# MainBoardNew.net
KiCad netlist of a schematic drawn in Altium Designer
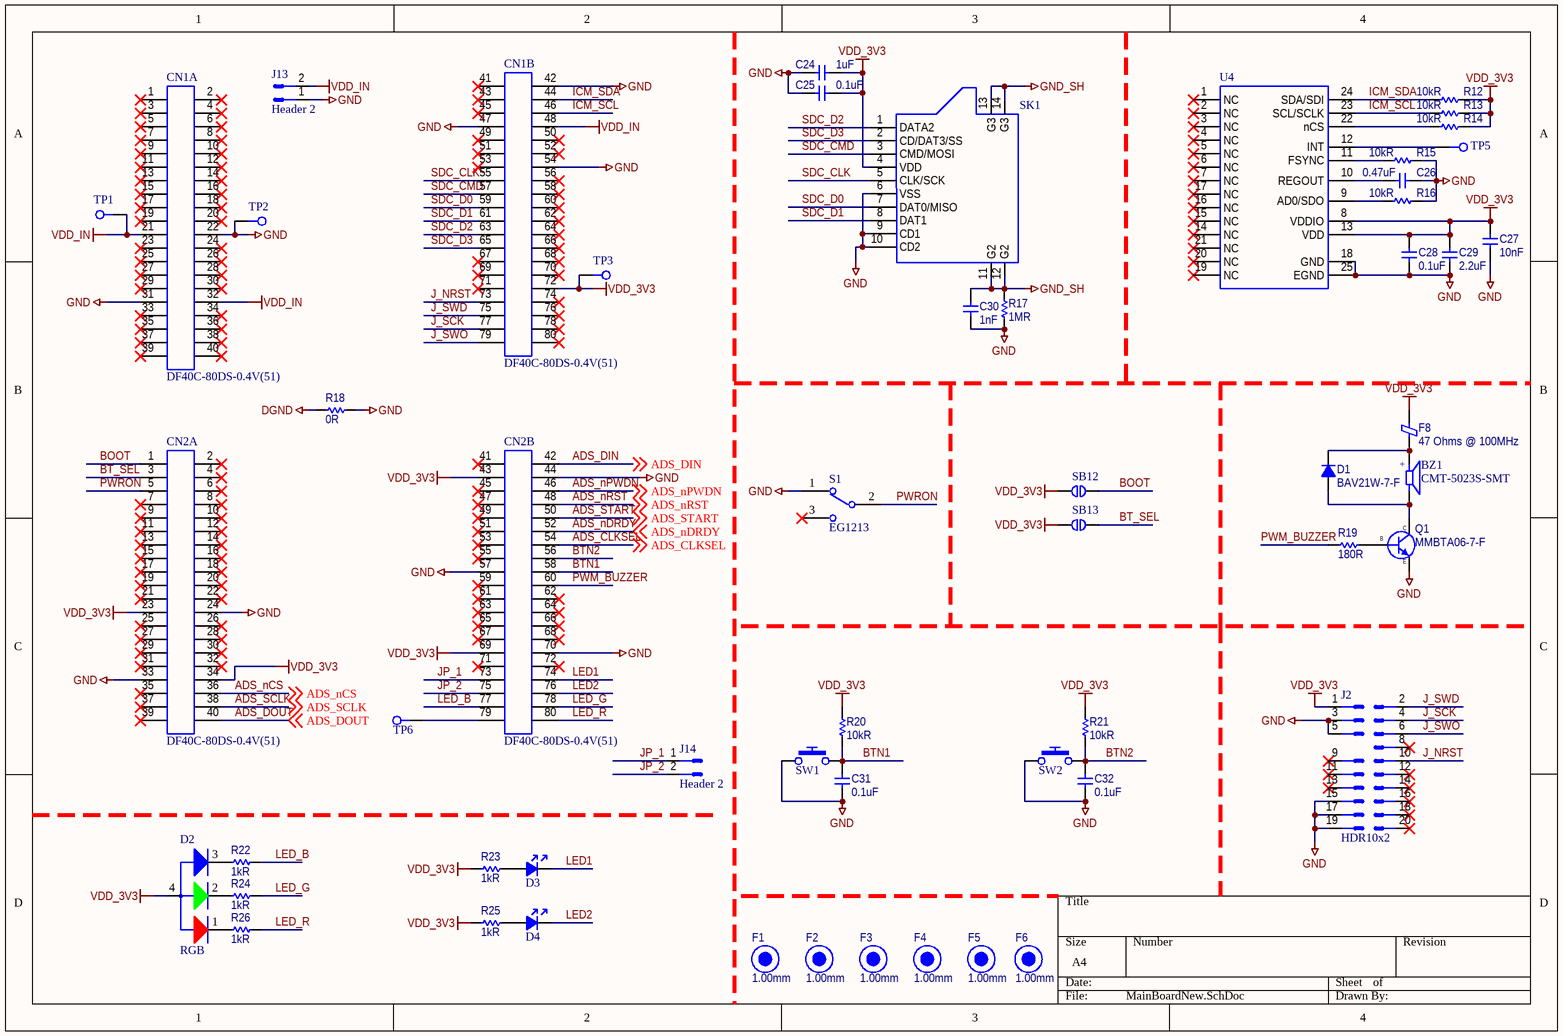
[diagram p0: MainBoardNew.SchDoc]

(export (version "E")
  (design (tool "Eeschema 10.0.6"))
  (components
    (comp (ref "BZ1")
      (value "CMT-5023S-SMT")
      (footprint "CUI_CMT-5023S-SMT")
      (description "AUDIO MAGNETIC XDCR 2-4V SMD")
      (fields
        (field (name "MANUFACTURER") "CUI Devices")
        (field (name "MANUFACTURER PART NUMBER") "CMT-5023S-SMT-TR")
      )
      (libsource (lib "DungMV") (part "CMT-5023S-SMT"))
    )
    (comp (ref "C24")
      (value "1uF")
      (footprint "C1005X04N")
      (description "CAP CER,1UF,10%,16V,X5R,0402,SMD")
      (fields
        (field (name "MANUFACTURER PART NUMBER") "EMK105BJ105KV-F")
        (field (name "MANUFACTURER") "Taiyo Yuden")
      )
      (libsource (lib "Database Library") (part "C_CAPN"))
    )
    (comp (ref "C25")
      (value "0.1uF")
      (footprint "C1005X04N")
      (description "CAP CER,0.1UF,20%,25V,X5R,0402,SMD")
      (fields
        (field (name "MANUFACTURER PART NUMBER") "TMK105BJ104MV-F")
        (field (name "MANUFACTURER") "Taiyo Yuden")
      )
      (libsource (lib "Database Library") (part "C_CAPN"))
    )
    (comp (ref "C26")
      (value "0.47uF")
      (footprint "C1005X04N")
      (description "CAP CER,0.47UF,10%,25V,X5R,0402,SMD")
      (fields
        (field (name "MANUFACTURER PART NUMBER") "TMK105ABJ474KVHF")
        (field (name "MANUFACTURER") "Taiyo Yuden")
      )
      (libsource (lib "Database Library") (part "C_CAPN"))
    )
    (comp (ref "C27")
      (value "10nF")
      (footprint "C1005X04N")
      (description "CAP CER,10NF,10%,50V,X7R,0402,SMD")
      (fields
        (field (name "MANUFACTURER PART NUMBER") "UMK105B7103KV-F")
        (field (name "MANUFACTURER") "Taiyo Yuden")
      )
      (libsource (lib "Database Library") (part "C_CAPN"))
    )
    (comp (ref "C28")
      (value "0.1uF")
      (footprint "C1005X04N")
      (description "CAP CER,0.1UF,20%,25V,X5R,0402,SMD")
      (fields
        (field (name "MANUFACTURER PART NUMBER") "TMK105BJ104MV-F")
        (field (name "MANUFACTURER") "Taiyo Yuden")
      )
      (libsource (lib "Database Library") (part "C_CAPN"))
    )
    (comp (ref "C29")
      (value "2.2uF")
      (footprint "C1005X04N")
      (description "CAP CER,2.2UF,20%,25V,X5R,0402,SMD")
      (fields
        (field (name "MANUFACTURER PART NUMBER") "TMK105CBJ225MV-F")
        (field (name "MANUFACTURER") "Taiyo Yuden")
      )
      (libsource (lib "Database Library") (part "C_CAPN"))
    )
    (comp (ref "C30")
      (value "1nF")
      (footprint "C1005X04N")
      (description "CAP CER,1NF,10%,50V,X7R,0402,SMD")
      (fields
        (field (name "MANUFACTURER PART NUMBER") "UMK105B7102KV-F")
        (field (name "MANUFACTURER") "Taiyo Yuden")
      )
      (libsource (lib "Database Library") (part "C_CAPN"))
    )
    (comp (ref "C31")
      (value "0.1uF")
      (footprint "C1005X04N")
      (description "CAP CER,0.1UF,20%,25V,X5R,0402,SMD")
      (fields
        (field (name "MANUFACTURER PART NUMBER") "TMK105BJ104MV-F")
        (field (name "MANUFACTURER") "Taiyo Yuden")
      )
      (libsource (lib "Database Library") (part "C_CAPN"))
    )
    (comp (ref "C32")
      (value "0.1uF")
      (footprint "C1005X04N")
      (description "CAP CER,0.1UF,20%,25V,X5R,0402,SMD")
      (fields
        (field (name "MANUFACTURER PART NUMBER") "TMK105BJ104MV-F")
        (field (name "MANUFACTURER") "Taiyo Yuden")
      )
      (libsource (lib "Database Library") (part "C_CAPN"))
    )
    (comp (ref "CN1")
      (value "DF40C-80DS-0.4V(51)")
      (footprint "DF40C-80DS-0.4V(51)")
      (description "CONN RCPT 80POS SMD GOLD")
      (fields (field (name "MANUFACTURER") "Hirose Electric Co Ltd"))
      (libsource (lib "DungMV") (part "DF40C-80DS-0.4V(51)"))
    )
    (comp (ref "CN2")
      (value "DF40C-80DS-0.4V(51)")
      (footprint "DF40C-80DS-0.4V(51)")
      (description "CONN RCPT 80POS SMD GOLD")
      (fields (field (name "MANUFACTURER") "Hirose Electric Co Ltd"))
      (libsource (lib "DungMV") (part "DF40C-80DS-0.4V(51)"))
    )
    (comp (ref "D1")
      (value "BAV21W-7-F")
      (footprint "SOD123")
      (description "DIODE,200V,200MA,1-CH,ID,SOD-123,SMD")
      (fields (field (name "MANUFACTURER") "Diodes Incorporated"))
      (libsource (lib "Database Library") (part "D_STD"))
    )
    (comp (ref "D2")
      (value "RGB")
      (footprint "LED 3528 PLCC4 RGB")
      (description "3528 PLCC4 RGB")
      (fields
        (field (name "MANUFACTURER") "American Bright Optoelectronics Corporation")
        (field (name "MANUFACTURER PART NUMBER") "BL-HJXGXBX32M-A")
      )
      (libsource (lib "DungMV") (part "BL-HJXGXBX32M-A"))
    )
    (comp (ref "D3")
      (value "LED BLUE")
      (footprint "LED0603")
      (description "LED BLUE CLEAR CHIP SMD")
      (libsource (lib "DungMV") (part "LTST-C191TBKT"))
    )
    (comp (ref "D4")
      (value "LED BLUE")
      (footprint "LED0603")
      (description "LED BLUE CLEAR CHIP SMD")
      (libsource (lib "DungMV") (part "LTST-C191TBKT"))
    )
    (comp (ref "F1")
      (value "1.00mm")
      (footprint "FIDUCIAL10-30")
      (description "FIDUCIAL,1.00mm,3.00mm")
      (fields
        (field (name "MANUFACTURER PART NUMBER") "FIDUCIAL10-30")
        (field (name "MANUFACTURER") "VNPT-Technology")
      )
      (libsource (lib "Database Library") (part "F_FIDUCIAL"))
    )
    (comp (ref "F2")
      (value "1.00mm")
      (footprint "FIDUCIAL10-30")
      (description "FIDUCIAL,1.00mm,3.00mm")
      (fields
        (field (name "MANUFACTURER PART NUMBER") "FIDUCIAL10-30")
        (field (name "MANUFACTURER") "VNPT-Technology")
      )
      (libsource (lib "Database Library") (part "F_FIDUCIAL"))
    )
    (comp (ref "F3")
      (value "1.00mm")
      (footprint "FIDUCIAL10-30")
      (description "FIDUCIAL,1.00mm,3.00mm")
      (fields
        (field (name "MANUFACTURER PART NUMBER") "FIDUCIAL10-30")
        (field (name "MANUFACTURER") "VNPT-Technology")
      )
      (libsource (lib "Database Library") (part "F_FIDUCIAL"))
    )
    (comp (ref "F4")
      (value "1.00mm")
      (footprint "FIDUCIAL10-30")
      (description "FIDUCIAL,1.00mm,3.00mm")
      (fields
        (field (name "MANUFACTURER PART NUMBER") "FIDUCIAL10-30")
        (field (name "MANUFACTURER") "VNPT-Technology")
      )
      (libsource (lib "Database Library") (part "F_FIDUCIAL"))
    )
    (comp (ref "F5")
      (value "1.00mm")
      (footprint "FIDUCIAL10-30")
      (description "FIDUCIAL,1.00mm,3.00mm")
      (fields
        (field (name "MANUFACTURER PART NUMBER") "FIDUCIAL10-30")
        (field (name "MANUFACTURER") "VNPT-Technology")
      )
      (libsource (lib "Database Library") (part "F_FIDUCIAL"))
    )
    (comp (ref "F6")
      (value "1.00mm")
      (footprint "FIDUCIAL10-30")
      (description "FIDUCIAL,1.00mm,3.00mm")
      (fields
        (field (name "MANUFACTURER PART NUMBER") "FIDUCIAL10-30")
        (field (name "MANUFACTURER") "VNPT-Technology")
      )
      (libsource (lib "Database Library") (part "F_FIDUCIAL"))
    )
    (comp (ref "F8")
      (value "47 Ohms @ 100MHz")
      (footprint "F2012X06N")
      (description "FERRITE BEAD,47 OHMS @ 100MHZ,0.05R,1A,0805,SMD")
      (fields
        (field (name "MANUFACTURER PART NUMBER") "BK2125HS470-T")
        (field (name "MANUFACTURER") "Taiyo Yuden")
      )
      (libsource (lib "Database Library") (part "F_FERRITE_BEAD"))
    )
    (comp (ref "J2")
      (value "HDR10x2")
      (footprint "FTSH-110-01-L-DV-007-P-TR")
      (description "CONN HEADER SMD 20POS 1.27MM")
      (libsource (lib "DungMV") (part "FTSH-110-01-L-DV-007-P-TR"))
    )
    (comp (ref "J13") (value "Header 2") (footprint "HDR1x2") (libsource (lib "DungMV") (part "Header 2")))
    (comp (ref "J14") (value "Header 2") (footprint "HDR1x2") (libsource (lib "DungMV") (part "Header 2")))
    (comp (ref "Q1")
      (value "MMBTA06-7-F")
      (footprint "SOT95P245X110-3N")
      (description "BJT NPN,80V,500MA,SOT23-3,SMD")
      (fields (field (name "MANUFACTURER") "Diodes Incorporated"))
      (libsource (lib "Database Library") (part "Q_NPN"))
    )
    (comp (ref "R12")
      (value "10kR")
      (footprint "R1005X04N")
      (description "RES,10KR,1%,62.5MW,0402,SMD")
      (fields
        (field (name "MANUFACTURER PART NUMBER") "RC0402FR-0710KL")
        (field (name "MANUFACTURER") "Yageo")
      )
      (libsource (lib "Database Library") (part "R_RES"))
    )
    (comp (ref "R13")
      (value "10kR")
      (footprint "R1005X04N")
      (description "RES,10KR,1%,62.5MW,0402,SMD")
      (fields
        (field (name "MANUFACTURER PART NUMBER") "RC0402FR-0710KL")
        (field (name "MANUFACTURER") "Yageo")
      )
      (libsource (lib "Database Library") (part "R_RES"))
    )
    (comp (ref "R14")
      (value "10kR")
      (footprint "R1005X04N")
      (description "RES,10KR,1%,62.5MW,0402,SMD")
      (fields
        (field (name "MANUFACTURER PART NUMBER") "RC0402FR-0710KL")
        (field (name "MANUFACTURER") "Yageo")
      )
      (libsource (lib "Database Library") (part "R_RES"))
    )
    (comp (ref "R15")
      (value "10kR")
      (footprint "R1005X04N")
      (description "RES,10KR,1%,62.5MW,0402,SMD")
      (fields
        (field (name "MANUFACTURER PART NUMBER") "RC0402FR-0710KL")
        (field (name "MANUFACTURER") "Yageo")
      )
      (libsource (lib "Database Library") (part "R_RES"))
    )
    (comp (ref "R16")
      (value "10kR")
      (footprint "R1005X04N")
      (description "RES,10KR,1%,62.5MW,0402,SMD")
      (fields
        (field (name "MANUFACTURER PART NUMBER") "RC0402FR-0710KL")
        (field (name "MANUFACTURER") "Yageo")
      )
      (libsource (lib "Database Library") (part "R_RES"))
    )
    (comp (ref "R17")
      (value "1MR")
      (footprint "R1005X04N")
      (description "RES,1MR,1%,62.5MW,0402,SMD")
      (fields
        (field (name "MANUFACTURER PART NUMBER") "RC0402FR-071ML")
        (field (name "MANUFACTURER") "Yageo")
      )
      (libsource (lib "Database Library") (part "R_RES"))
    )
    (comp (ref "R18")
      (value "0R")
      (footprint "R1005X04N")
      (description "RES,0R,JUMPER,62.5MW,0402,SMD")
      (fields
        (field (name "MANUFACTURER PART NUMBER") "RC0402FR-070RL")
        (field (name "MANUFACTURER") "Yageo")
      )
      (libsource (lib "Database Library") (part "R_RES"))
    )
    (comp (ref "R19")
      (value "180R")
      (footprint "R1005X04N")
      (description "RES,180R,1%,200MW,0402,SMD")
      (fields
        (field (name "MANUFACTURER PART NUMBER") "CRCW0402180RFKEDHP")
        (field (name "MANUFACTURER") "Vishay / Dale")
      )
      (libsource (lib "Database Library") (part "R_RES"))
    )
    (comp (ref "R20")
      (value "10kR")
      (footprint "R1005X04N")
      (description "RES,10KR,1%,62.5MW,0402,SMD")
      (fields
        (field (name "MANUFACTURER PART NUMBER") "RC0402FR-0710KL")
        (field (name "MANUFACTURER") "Yageo")
      )
      (libsource (lib "Database Library") (part "R_RES"))
    )
    (comp (ref "R21")
      (value "10kR")
      (footprint "R1005X04N")
      (description "RES,10KR,1%,62.5MW,0402,SMD")
      (fields
        (field (name "MANUFACTURER PART NUMBER") "RC0402FR-0710KL")
        (field (name "MANUFACTURER") "Yageo")
      )
      (libsource (lib "Database Library") (part "R_RES"))
    )
    (comp (ref "R22")
      (value "1kR")
      (footprint "R1005X04N")
      (description "RES,1KR,5%,62.5MW,0402,SMD")
      (fields
        (field (name "MANUFACTURER PART NUMBER") "RC0402JR-071KL")
        (field (name "MANUFACTURER") "Yageo")
      )
      (libsource (lib "Database Library") (part "R_RES"))
    )
    (comp (ref "R23")
      (value "1kR")
      (footprint "R1005X04N")
      (description "RES,1KR,5%,62.5MW,0402,SMD")
      (fields
        (field (name "MANUFACTURER PART NUMBER") "RC0402JR-071KL")
        (field (name "MANUFACTURER") "Yageo")
      )
      (libsource (lib "Database Library") (part "R_RES"))
    )
    (comp (ref "R24")
      (value "1kR")
      (footprint "R1005X04N")
      (description "RES,1KR,5%,62.5MW,0402,SMD")
      (fields
        (field (name "MANUFACTURER PART NUMBER") "RC0402JR-071KL")
        (field (name "MANUFACTURER") "Yageo")
      )
      (libsource (lib "Database Library") (part "R_RES"))
    )
    (comp (ref "R25")
      (value "1kR")
      (footprint "R1005X04N")
      (description "RES,1KR,5%,62.5MW,0402,SMD")
      (fields
        (field (name "MANUFACTURER PART NUMBER") "RC0402JR-071KL")
        (field (name "MANUFACTURER") "Yageo")
      )
      (libsource (lib "Database Library") (part "R_RES"))
    )
    (comp (ref "R26")
      (value "1kR")
      (footprint "R1005X04N")
      (description "RES,1KR,5%,62.5MW,0402,SMD")
      (fields
        (field (name "MANUFACTURER PART NUMBER") "RC0402JR-071KL")
        (field (name "MANUFACTURER") "Yageo")
      )
      (libsource (lib "Database Library") (part "R_RES"))
    )
    (comp (ref "S1")
      (value "EG1213")
      (footprint "SW_EG1213")
      (description "SWITCH SLIDE SPDT 200MA 30V")
      (fields (field (name "MANUFACTURER") "E-Switch"))
      (libsource (lib "DungMV") (part "EG1213"))
    )
    (comp (ref "SB12")
      (value "Solder Jump")
      (footprint "SJB_0603")
      (description "Solder Bridge Jumper 0603")
      (libsource (lib "DungMV") (part "Solder Jump"))
    )
    (comp (ref "SB13")
      (value "Solder Jump")
      (footprint "SJB_0603")
      (description "Solder Bridge Jumper 0603")
      (libsource (lib "DungMV") (part "Solder Jump"))
    )
    (comp (ref "SK1")
      (value "MICRO SD CARD")
      (footprint "114-00841-68")
      (description "CONN MICRO SD CARD PUSH-PULL R/A")
      (fields
        (field (name "MANUFACTURER") "Amphenol ICC (Commercial Products)")
        (field (name "MANUFACTURER PART NUMBER") "114-00841-68")
      )
      (libsource (lib "DungMV") (part "114-00841-68"))
    )
    (comp (ref "SW1")
      (value "FSMRA4JH04")
      (footprint "1-1825027-1")
      (description "SWITCH TACTILE SPST-NO 0.05A 24V")
      (fields (field (name "MANUFACTURER") "TE Connectivity"))
      (libsource (lib "DungMV") (part "FSMRA4JH04"))
    )
    (comp (ref "SW2")
      (value "FSMRA4JH04")
      (footprint "1-1825027-1")
      (description "SWITCH TACTILE SPST-NO 0.05A 24V")
      (fields (field (name "MANUFACTURER") "TE Connectivity"))
      (libsource (lib "DungMV") (part "FSMRA4JH04"))
    )
    (comp (ref "TP1")
      (value "TP_25MILC")
      (footprint "TESTPOINT_1MM")
      (description "Test Point 25mil")
      (libsource (lib "DungMV") (part "TP_25MILC"))
    )
    (comp (ref "TP2")
      (value "TP_25MILC")
      (footprint "TESTPOINT_1MM")
      (description "Test Point 25mil")
      (libsource (lib "DungMV") (part "TP_25MILC"))
    )
    (comp (ref "TP3")
      (value "TP_25MILC")
      (footprint "TESTPOINT_1MM")
      (description "Test Point 25mil")
      (libsource (lib "DungMV") (part "TP_25MILC"))
    )
    (comp (ref "TP5")
      (value "TP_25MILC")
      (footprint "TESTPOINT_1MM")
      (description "Test Point 25mil")
      (libsource (lib "DungMV") (part "TP_25MILC"))
    )
    (comp (ref "TP6")
      (value "TP_25MILC")
      (footprint "TESTPOINT_1MM")
      (description "Test Point 25mil")
      (libsource (lib "DungMV") (part "TP_25MILC"))
    )
    (comp (ref "U4")
      (value "ICM-20689")
      (footprint "QFN50P400X400X100_HS-25N-NP")
      (description "IMU ACCEL/GYRO/MAG I2C/SPI 24QFN")
      (fields (field (name "MANUFACTURER") "TDK InvenSense"))
      (libsource (lib "DungMV") (part "ICM-20689"))
    )
  )
  (nets
    (net (code "1") (name "/BOOT") (class "Default")
      (node (ref "CN2") (pin "1") (pinfunction "1_1") (pintype "passive"))
      (node (ref "SB12") (pin "1") (pinfunction "1_1") (pintype "passive"))
    )
    (net (code "2") (name "/BTN1") (class "Default")
      (node (ref "C31") (pin "2") (pinfunction "2_2") (pintype "passive"))
      (node (ref "CN2") (pin "58") (pinfunction "58_58") (pintype "passive"))
      (node (ref "R20") (pin "1") (pinfunction "1_1") (pintype "passive"))
      (node (ref "SW1") (pin "2") (pinfunction "2_2") (pintype "passive"))
    )
    (net (code "3") (name "/BTN2") (class "Default")
      (node (ref "C32") (pin "2") (pinfunction "2_2") (pintype "passive"))
      (node (ref "CN2") (pin "56") (pinfunction "56_56") (pintype "passive"))
      (node (ref "R21") (pin "1") (pinfunction "1_1") (pintype "passive"))
      (node (ref "SW2") (pin "2") (pinfunction "2_2") (pintype "passive"))
    )
    (net (code "4") (name "/BT_SEL") (class "Default")
      (node (ref "CN2") (pin "3") (pinfunction "3_3") (pintype "passive"))
      (node (ref "SB13") (pin "1") (pinfunction "1_1") (pintype "passive"))
    )
    (net (code "5") (name "/ICM_SCL") (class "Default")
      (node (ref "CN1") (pin "46") (pinfunction "46_46") (pintype "passive"))
      (node (ref "R13") (pin "2") (pinfunction "2_2") (pintype "passive"))
      (node (ref "U4") (pin "23") (pinfunction "SCL/SCLK_23") (pintype "passive"))
    )
    (net (code "6") (name "/ICM_SDA") (class "Default")
      (node (ref "CN1") (pin "44") (pinfunction "44_44") (pintype "passive"))
      (node (ref "R12") (pin "2") (pinfunction "2_2") (pintype "passive"))
      (node (ref "U4") (pin "24") (pinfunction "SDA/SDI_24") (pintype "passive"))
    )
    (net (code "7") (name "/JP_1") (class "Default")
      (node (ref "CN2") (pin "73") (pinfunction "73_73") (pintype "passive"))
      (node (ref "J14") (pin "1") (pinfunction "1_1") (pintype "passive"))
    )
    (net (code "8") (name "/JP_2") (class "Default")
      (node (ref "CN2") (pin "75") (pinfunction "75_75") (pintype "passive"))
      (node (ref "J14") (pin "2") (pinfunction "2_2") (pintype "passive"))
    )
    (net (code "9") (name "/J_NRST") (class "Default")
      (node (ref "CN1") (pin "73") (pinfunction "73_73") (pintype "passive"))
      (node (ref "J2") (pin "10") (pinfunction "10_10") (pintype "passive"))
    )
    (net (code "10") (name "/J_SCK") (class "Default")
      (node (ref "CN1") (pin "77") (pinfunction "77_77") (pintype "passive"))
      (node (ref "J2") (pin "4") (pinfunction "4_4") (pintype "passive"))
    )
    (net (code "11") (name "/J_SWD") (class "Default")
      (node (ref "CN1") (pin "75") (pinfunction "75_75") (pintype "passive"))
      (node (ref "J2") (pin "2") (pinfunction "2_2") (pintype "passive"))
    )
    (net (code "12") (name "/J_SWO") (class "Default")
      (node (ref "CN1") (pin "79") (pinfunction "79_79") (pintype "passive"))
      (node (ref "J2") (pin "6") (pinfunction "6_6") (pintype "passive"))
    )
    (net (code "13") (name "/LED1") (class "Default")
      (node (ref "CN2") (pin "74") (pinfunction "74_74") (pintype "passive"))
      (node (ref "D3") (pin "2") (pinfunction "K_2") (pintype "passive"))
    )
    (net (code "14") (name "/LED2") (class "Default")
      (node (ref "CN2") (pin "76") (pinfunction "76_76") (pintype "passive"))
      (node (ref "D4") (pin "2") (pinfunction "K_2") (pintype "passive"))
    )
    (net (code "15") (name "/LED_B") (class "Default")
      (node (ref "CN2") (pin "77") (pinfunction "77_77") (pintype "passive"))
      (node (ref "R22") (pin "2") (pinfunction "2_2") (pintype "passive"))
    )
    (net (code "16") (name "/LED_G") (class "Default")
      (node (ref "CN2") (pin "78") (pinfunction "78_78") (pintype "passive"))
      (node (ref "R24") (pin "2") (pinfunction "2_2") (pintype "passive"))
    )
    (net (code "17") (name "/LED_R") (class "Default")
      (node (ref "CN2") (pin "80") (pinfunction "80_80") (pintype "passive"))
      (node (ref "R26") (pin "2") (pinfunction "2_2") (pintype "passive"))
    )
    (net (code "18") (name "/PWM_BUZZER") (class "Default")
      (node (ref "CN2") (pin "60") (pinfunction "60_60") (pintype "passive"))
      (node (ref "R19") (pin "1") (pinfunction "1_1") (pintype "passive"))
    )
    (net (code "19") (name "/PWRON") (class "Default")
      (node (ref "CN2") (pin "5") (pinfunction "5_5") (pintype "passive"))
      (node (ref "S1") (pin "2") (pinfunction "2_2") (pintype "passive"))
    )
    (net (code "20") (name "/SDC_CLK") (class "Default")
      (node (ref "CN1") (pin "55") (pinfunction "55_55") (pintype "passive"))
      (node (ref "SK1") (pin "5") (pinfunction "CLK/SCK_5") (pintype "passive"))
    )
    (net (code "21") (name "/SDC_CMD") (class "Default")
      (node (ref "CN1") (pin "57") (pinfunction "57_57") (pintype "passive"))
      (node (ref "SK1") (pin "3") (pinfunction "CMD/MOSI_3") (pintype "passive"))
    )
    (net (code "22") (name "/SDC_D0") (class "Default")
      (node (ref "CN1") (pin "59") (pinfunction "59_59") (pintype "passive"))
      (node (ref "SK1") (pin "7") (pinfunction "DAT0/MISO_7") (pintype "passive"))
    )
    (net (code "23") (name "/SDC_D1") (class "Default")
      (node (ref "CN1") (pin "61") (pinfunction "61_61") (pintype "passive"))
      (node (ref "SK1") (pin "8") (pinfunction "DAT1_8") (pintype "passive"))
    )
    (net (code "24") (name "/SDC_D2") (class "Default")
      (node (ref "CN1") (pin "63") (pinfunction "63_63") (pintype "passive"))
      (node (ref "SK1") (pin "1") (pinfunction "DATA2_1") (pintype "passive"))
    )
    (net (code "25") (name "/SDC_D3") (class "Default")
      (node (ref "CN1") (pin "65") (pinfunction "65_65") (pintype "passive"))
      (node (ref "SK1") (pin "2") (pinfunction "CD/DAT3/SS_2") (pintype "passive"))
    )
    (net (code "26") (name "ADS_CLKSEL") (class "Default")
      (node (ref "CN2") (pin "54") (pinfunction "54_54") (pintype "passive"))
    )
    (net (code "27") (name "ADS_DIN") (class "Default")
      (node (ref "CN2") (pin "42") (pinfunction "42_42") (pintype "passive"))
    )
    (net (code "28") (name "ADS_DOUT") (class "Default")
      (node (ref "CN2") (pin "40") (pinfunction "40_40") (pintype "passive"))
    )
    (net (code "29") (name "ADS_SCLK") (class "Default")
      (node (ref "CN2") (pin "38") (pinfunction "38_38") (pintype "passive"))
    )
    (net (code "30") (name "ADS_START") (class "Default")
      (node (ref "CN2") (pin "50") (pinfunction "50_50") (pintype "passive"))
    )
    (net (code "31") (name "ADS_nCS") (class "Default")
      (node (ref "CN2") (pin "36") (pinfunction "36_36") (pintype "passive"))
    )
    (net (code "32") (name "ADS_nDRDY") (class "Default")
      (node (ref "CN2") (pin "52") (pinfunction "52_52") (pintype "passive"))
    )
    (net (code "33") (name "ADS_nPWDN") (class "Default")
      (node (ref "CN2") (pin "46") (pinfunction "46_46") (pintype "passive"))
    )
    (net (code "34") (name "ADS_nRST") (class "Default")
      (node (ref "CN2") (pin "48") (pinfunction "48_48") (pintype "passive"))
    )
    (net (code "35") (name "DGND") (class "Default")
      (node (ref "R18") (pin "1") (pinfunction "1_1") (pintype "passive"))
    )
    (net (code "36") (name "GND") (class "Default")
      (node (ref "C24") (pin "1") (pinfunction "1_1") (pintype "passive"))
      (node (ref "C25") (pin "2") (pinfunction "2_2") (pintype "passive"))
      (node (ref "C26") (pin "2") (pinfunction "2_2") (pintype "passive"))
      (node (ref "C27") (pin "1") (pinfunction "1_1") (pintype "passive"))
      (node (ref "C28") (pin "2") (pinfunction "2_2") (pintype "passive"))
      (node (ref "C29") (pin "1") (pinfunction "1_1") (pintype "passive"))
      (node (ref "C30") (pin "1") (pinfunction "1_1") (pintype "passive"))
      (node (ref "C31") (pin "1") (pinfunction "1_1") (pintype "passive"))
      (node (ref "C32") (pin "1") (pinfunction "1_1") (pintype "passive"))
      (node (ref "CN1") (pin "22") (pinfunction "22_22") (pintype "passive"))
      (node (ref "CN1") (pin "31") (pinfunction "31_31") (pintype "passive"))
      (node (ref "CN1") (pin "42") (pinfunction "42_42") (pintype "passive"))
      (node (ref "CN1") (pin "47") (pinfunction "47_47") (pintype "passive"))
      (node (ref "CN1") (pin "54") (pinfunction "54_54") (pintype "passive"))
      (node (ref "CN2") (pin "24") (pinfunction "24_24") (pintype "passive"))
      (node (ref "CN2") (pin "33") (pinfunction "33_33") (pintype "passive"))
      (node (ref "CN2") (pin "44") (pinfunction "44_44") (pintype "passive"))
      (node (ref "CN2") (pin "57") (pinfunction "57_57") (pintype "passive"))
      (node (ref "CN2") (pin "70") (pinfunction "70_70") (pintype "passive"))
      (node (ref "J13") (pin "1") (pinfunction "1_1") (pintype "passive"))
      (node (ref "J2") (pin "15") (pinfunction "15_15") (pintype "passive"))
      (node (ref "J2") (pin "17") (pinfunction "17_17") (pintype "passive"))
      (node (ref "J2") (pin "19") (pinfunction "19_19") (pintype "passive"))
      (node (ref "J2") (pin "3") (pinfunction "3_3") (pintype "passive"))
      (node (ref "J2") (pin "5") (pinfunction "5_5") (pintype "passive"))
      (node (ref "Q1") (pin "2") (pinfunction "E_2") (pintype "passive"))
      (node (ref "R15") (pin "1") (pinfunction "1_1") (pintype "passive"))
      (node (ref "R16") (pin "1") (pinfunction "1_1") (pintype "passive"))
      (node (ref "R17") (pin "1") (pinfunction "1_1") (pintype "passive"))
      (node (ref "R18") (pin "2") (pinfunction "2_2") (pintype "passive"))
      (node (ref "S1") (pin "1") (pinfunction "1_1") (pintype "passive"))
      (node (ref "SK1") (pin "10") (pinfunction "CD2_10") (pintype "passive"))
      (node (ref "SK1") (pin "6") (pinfunction "VSS_6") (pintype "power_in"))
      (node (ref "SK1") (pin "9") (pinfunction "CD1_9") (pintype "passive"))
      (node (ref "SW1") (pin "1") (pinfunction "1_1") (pintype "passive"))
      (node (ref "SW2") (pin "1") (pinfunction "1_1") (pintype "passive"))
      (node (ref "TP2") (pin "1") (pinfunction "1_1") (pintype "passive"))
      (node (ref "U4") (pin "18") (pinfunction "GND_18") (pintype "passive"))
      (node (ref "U4") (pin "25") (pinfunction "EGND_25") (pintype "passive"))
    )
    (net (code "37") (name "GND_SH") (class "Default")
      (node (ref "C30") (pin "2") (pinfunction "2_2") (pintype "passive"))
      (node (ref "R17") (pin "2") (pinfunction "2_2") (pintype "passive"))
      (node (ref "SK1") (pin "11") (pinfunction "G2_11") (pintype "power_in"))
      (node (ref "SK1") (pin "12") (pinfunction "G2_12") (pintype "power_in"))
      (node (ref "SK1") (pin "13") (pinfunction "G3_13") (pintype "power_in"))
      (node (ref "SK1") (pin "14") (pinfunction "G3_14") (pintype "power_in"))
    )
    (net (code "38") (name "Net-(CN2-Pad79)") (class "Default")
      (node (ref "CN2") (pin "79") (pinfunction "79_79") (pintype "passive"))
      (node (ref "TP6") (pin "1") (pinfunction "1_1") (pintype "passive"))
    )
    (net (code "39") (name "Net-(D1-A)") (class "Default")
      (node (ref "BZ1") (pin "N") (pinfunction "N_N") (pintype "passive"))
      (node (ref "D1") (pin "2") (pinfunction "A_2") (pintype "passive"))
      (node (ref "Q1") (pin "3") (pinfunction "C_3") (pintype "passive"))
    )
    (net (code "40") (name "Net-(D1-C)") (class "Default")
      (node (ref "BZ1") (pin "P") (pinfunction "P_P") (pintype "passive"))
      (node (ref "D1") (pin "1") (pinfunction "C_1") (pintype "passive"))
      (node (ref "F8") (pin "1") (pinfunction "1_1") (pintype "passive"))
    )
    (net (code "41") (name "Net-(D2-CATHODE_BLUE)") (class "Default")
      (node (ref "D2") (pin "3") (pinfunction "CATHODE_BLUE_3") (pintype "passive"))
      (node (ref "R22") (pin "1") (pinfunction "1_1") (pintype "passive"))
    )
    (net (code "42") (name "Net-(D2-CATHODE_GREEN)") (class "Default")
      (node (ref "D2") (pin "2") (pinfunction "CATHODE_GREEN_2") (pintype "passive"))
      (node (ref "R24") (pin "1") (pinfunction "1_1") (pintype "passive"))
    )
    (net (code "43") (name "Net-(D2-CATHODE_RED)") (class "Default")
      (node (ref "D2") (pin "1") (pinfunction "CATHODE_RED_1") (pintype "passive"))
      (node (ref "R26") (pin "1") (pinfunction "1_1") (pintype "passive"))
    )
    (net (code "44") (name "Net-(D3-A)") (class "Default")
      (node (ref "D3") (pin "1") (pinfunction "A_1") (pintype "passive"))
      (node (ref "R23") (pin "2") (pinfunction "2_2") (pintype "passive"))
    )
    (net (code "45") (name "Net-(D4-A)") (class "Default")
      (node (ref "D4") (pin "1") (pinfunction "A_1") (pintype "passive"))
      (node (ref "R25") (pin "2") (pinfunction "2_2") (pintype "passive"))
    )
    (net (code "46") (name "Net-(Q1-B)") (class "Default")
      (node (ref "Q1") (pin "1") (pinfunction "B_1") (pintype "passive"))
      (node (ref "R19") (pin "2") (pinfunction "2_2") (pintype "passive"))
    )
    (net (code "47") (name "Net-(U4-AD0{slash}SDO)") (class "Default")
      (node (ref "R16") (pin "2") (pinfunction "2_2") (pintype "passive"))
      (node (ref "U4") (pin "9") (pinfunction "AD0/SDO_9") (pintype "passive"))
    )
    (net (code "48") (name "Net-(U4-FSYNC)") (class "Default")
      (node (ref "R15") (pin "2") (pinfunction "2_2") (pintype "passive"))
      (node (ref "U4") (pin "11") (pinfunction "FSYNC_11") (pintype "passive"))
    )
    (net (code "49") (name "Net-(U4-INT)") (class "Default")
      (node (ref "TP5") (pin "1") (pinfunction "1_1") (pintype "passive"))
      (node (ref "U4") (pin "12") (pinfunction "INT_12") (pintype "passive"))
    )
    (net (code "50") (name "Net-(U4-REGOUT)") (class "Default")
      (node (ref "C26") (pin "1") (pinfunction "1_1") (pintype "passive"))
      (node (ref "U4") (pin "10") (pinfunction "REGOUT_10") (pintype "passive"))
    )
    (net (code "51") (name "Net-(U4-nCS)") (class "Default")
      (node (ref "R14") (pin "2") (pinfunction "2_2") (pintype "passive"))
      (node (ref "U4") (pin "22") (pinfunction "nCS_22") (pintype "passive"))
    )
    (net (code "52") (name "VDD_3V3") (class "Default")
      (node (ref "C24") (pin "2") (pinfunction "2_2") (pintype "passive"))
      (node (ref "C25") (pin "1") (pinfunction "1_1") (pintype "passive"))
      (node (ref "C27") (pin "2") (pinfunction "2_2") (pintype "passive"))
      (node (ref "C28") (pin "1") (pinfunction "1_1") (pintype "passive"))
      (node (ref "C29") (pin "2") (pinfunction "2_2") (pintype "passive"))
      (node (ref "CN1") (pin "72") (pinfunction "72_72") (pintype "passive"))
      (node (ref "CN2") (pin "23") (pinfunction "23_23") (pintype "passive"))
      (node (ref "CN2") (pin "34") (pinfunction "34_34") (pintype "passive"))
      (node (ref "CN2") (pin "43") (pinfunction "43_43") (pintype "passive"))
      (node (ref "CN2") (pin "69") (pinfunction "69_69") (pintype "passive"))
      (node (ref "D2") (pin "4") (pinfunction "COMM_ANODE_4") (pintype "passive"))
      (node (ref "F8") (pin "2") (pinfunction "2_2") (pintype "passive"))
      (node (ref "J2") (pin "1") (pinfunction "1_1") (pintype "passive"))
      (node (ref "R12") (pin "1") (pinfunction "1_1") (pintype "passive"))
      (node (ref "R13") (pin "1") (pinfunction "1_1") (pintype "passive"))
      (node (ref "R14") (pin "1") (pinfunction "1_1") (pintype "passive"))
      (node (ref "R20") (pin "2") (pinfunction "2_2") (pintype "passive"))
      (node (ref "R21") (pin "2") (pinfunction "2_2") (pintype "passive"))
      (node (ref "R23") (pin "1") (pinfunction "1_1") (pintype "passive"))
      (node (ref "R25") (pin "1") (pinfunction "1_1") (pintype "passive"))
      (node (ref "SB12") (pin "2") (pinfunction "2_2") (pintype "passive"))
      (node (ref "SB13") (pin "2") (pinfunction "2_2") (pintype "passive"))
      (node (ref "SK1") (pin "4") (pinfunction "VDD_4") (pintype "power_in"))
      (node (ref "TP3") (pin "1") (pinfunction "1_1") (pintype "passive"))
      (node (ref "U4") (pin "13") (pinfunction "VDD_13") (pintype "passive"))
      (node (ref "U4") (pin "8") (pinfunction "VDDIO_8") (pintype "passive"))
    )
    (net (code "53") (name "VDD_IN") (class "Default")
      (node (ref "CN1") (pin "21") (pinfunction "21_21") (pintype "passive"))
      (node (ref "CN1") (pin "32") (pinfunction "32_32") (pintype "passive"))
      (node (ref "CN1") (pin "48") (pinfunction "48_48") (pintype "passive"))
      (node (ref "J13") (pin "2") (pinfunction "2_2") (pintype "passive"))
      (node (ref "TP1") (pin "1") (pinfunction "1_1") (pintype "passive"))
    )
    (net (code "54") (name "unconnected-(CN1-Pad1)") (class "Default")
      (node (ref "CN1") (pin "1") (pinfunction "1_1") (pintype "passive+no_connect"))
    )
    (net (code "55") (name "unconnected-(CN1-Pad2)") (class "Default")
      (node (ref "CN1") (pin "2") (pinfunction "2_2") (pintype "passive+no_connect"))
    )
    (net (code "56") (name "unconnected-(CN1-Pad3)") (class "Default")
      (node (ref "CN1") (pin "3") (pinfunction "3_3") (pintype "passive+no_connect"))
    )
    (net (code "57") (name "unconnected-(CN1-Pad4)") (class "Default")
      (node (ref "CN1") (pin "4") (pinfunction "4_4") (pintype "passive+no_connect"))
    )
    (net (code "58") (name "unconnected-(CN1-Pad5)") (class "Default")
      (node (ref "CN1") (pin "5") (pinfunction "5_5") (pintype "passive+no_connect"))
    )
    (net (code "59") (name "unconnected-(CN1-Pad6)") (class "Default")
      (node (ref "CN1") (pin "6") (pinfunction "6_6") (pintype "passive+no_connect"))
    )
    (net (code "60") (name "unconnected-(CN1-Pad7)") (class "Default")
      (node (ref "CN1") (pin "7") (pinfunction "7_7") (pintype "passive+no_connect"))
    )
    (net (code "61") (name "unconnected-(CN1-Pad8)") (class "Default")
      (node (ref "CN1") (pin "8") (pinfunction "8_8") (pintype "passive+no_connect"))
    )
    (net (code "62") (name "unconnected-(CN1-Pad9)") (class "Default")
      (node (ref "CN1") (pin "9") (pinfunction "9_9") (pintype "passive+no_connect"))
    )
    (net (code "63") (name "unconnected-(CN1-Pad10)") (class "Default")
      (node (ref "CN1") (pin "10") (pinfunction "10_10") (pintype "passive+no_connect"))
    )
    (net (code "64") (name "unconnected-(CN1-Pad11)") (class "Default")
      (node (ref "CN1") (pin "11") (pinfunction "11_11") (pintype "passive+no_connect"))
    )
    (net (code "65") (name "unconnected-(CN1-Pad12)") (class "Default")
      (node (ref "CN1") (pin "12") (pinfunction "12_12") (pintype "passive+no_connect"))
    )
    (net (code "66") (name "unconnected-(CN1-Pad13)") (class "Default")
      (node (ref "CN1") (pin "13") (pinfunction "13_13") (pintype "passive+no_connect"))
    )
    (net (code "67") (name "unconnected-(CN1-Pad14)") (class "Default")
      (node (ref "CN1") (pin "14") (pinfunction "14_14") (pintype "passive+no_connect"))
    )
    (net (code "68") (name "unconnected-(CN1-Pad15)") (class "Default")
      (node (ref "CN1") (pin "15") (pinfunction "15_15") (pintype "passive+no_connect"))
    )
    (net (code "69") (name "unconnected-(CN1-Pad16)") (class "Default")
      (node (ref "CN1") (pin "16") (pinfunction "16_16") (pintype "passive+no_connect"))
    )
    (net (code "70") (name "unconnected-(CN1-Pad17)") (class "Default")
      (node (ref "CN1") (pin "17") (pinfunction "17_17") (pintype "passive+no_connect"))
    )
    (net (code "71") (name "unconnected-(CN1-Pad18)") (class "Default")
      (node (ref "CN1") (pin "18") (pinfunction "18_18") (pintype "passive+no_connect"))
    )
    (net (code "72") (name "unconnected-(CN1-Pad19)") (class "Default")
      (node (ref "CN1") (pin "19") (pinfunction "19_19") (pintype "passive+no_connect"))
    )
    (net (code "73") (name "unconnected-(CN1-Pad20)") (class "Default")
      (node (ref "CN1") (pin "20") (pinfunction "20_20") (pintype "passive+no_connect"))
    )
    (net (code "74") (name "unconnected-(CN1-Pad23)") (class "Default")
      (node (ref "CN1") (pin "23") (pinfunction "23_23") (pintype "passive+no_connect"))
    )
    (net (code "75") (name "unconnected-(CN1-Pad24)") (class "Default")
      (node (ref "CN1") (pin "24") (pinfunction "24_24") (pintype "passive+no_connect"))
    )
    (net (code "76") (name "unconnected-(CN1-Pad25)") (class "Default")
      (node (ref "CN1") (pin "25") (pinfunction "25_25") (pintype "passive+no_connect"))
    )
    (net (code "77") (name "unconnected-(CN1-Pad26)") (class "Default")
      (node (ref "CN1") (pin "26") (pinfunction "26_26") (pintype "passive+no_connect"))
    )
    (net (code "78") (name "unconnected-(CN1-Pad27)") (class "Default")
      (node (ref "CN1") (pin "27") (pinfunction "27_27") (pintype "passive+no_connect"))
    )
    (net (code "79") (name "unconnected-(CN1-Pad28)") (class "Default")
      (node (ref "CN1") (pin "28") (pinfunction "28_28") (pintype "passive+no_connect"))
    )
    (net (code "80") (name "unconnected-(CN1-Pad29)") (class "Default")
      (node (ref "CN1") (pin "29") (pinfunction "29_29") (pintype "passive+no_connect"))
    )
    (net (code "81") (name "unconnected-(CN1-Pad30)") (class "Default")
      (node (ref "CN1") (pin "30") (pinfunction "30_30") (pintype "passive+no_connect"))
    )
    (net (code "82") (name "unconnected-(CN1-Pad33)") (class "Default")
      (node (ref "CN1") (pin "33") (pinfunction "33_33") (pintype "passive+no_connect"))
    )
    (net (code "83") (name "unconnected-(CN1-Pad34)") (class "Default")
      (node (ref "CN1") (pin "34") (pinfunction "34_34") (pintype "passive+no_connect"))
    )
    (net (code "84") (name "unconnected-(CN1-Pad35)") (class "Default")
      (node (ref "CN1") (pin "35") (pinfunction "35_35") (pintype "passive+no_connect"))
    )
    (net (code "85") (name "unconnected-(CN1-Pad36)") (class "Default")
      (node (ref "CN1") (pin "36") (pinfunction "36_36") (pintype "passive+no_connect"))
    )
    (net (code "86") (name "unconnected-(CN1-Pad37)") (class "Default")
      (node (ref "CN1") (pin "37") (pinfunction "37_37") (pintype "passive+no_connect"))
    )
    (net (code "87") (name "unconnected-(CN1-Pad38)") (class "Default")
      (node (ref "CN1") (pin "38") (pinfunction "38_38") (pintype "passive+no_connect"))
    )
    (net (code "88") (name "unconnected-(CN1-Pad39)") (class "Default")
      (node (ref "CN1") (pin "39") (pinfunction "39_39") (pintype "passive+no_connect"))
    )
    (net (code "89") (name "unconnected-(CN1-Pad40)") (class "Default")
      (node (ref "CN1") (pin "40") (pinfunction "40_40") (pintype "passive+no_connect"))
    )
    (net (code "90") (name "unconnected-(CN1-Pad41)") (class "Default")
      (node (ref "CN1") (pin "41") (pinfunction "41_41") (pintype "passive+no_connect"))
    )
    (net (code "91") (name "unconnected-(CN1-Pad43)") (class "Default")
      (node (ref "CN1") (pin "43") (pinfunction "43_43") (pintype "passive+no_connect"))
    )
    (net (code "92") (name "unconnected-(CN1-Pad45)") (class "Default")
      (node (ref "CN1") (pin "45") (pinfunction "45_45") (pintype "passive+no_connect"))
    )
    (net (code "93") (name "unconnected-(CN1-Pad49)") (class "Default")
      (node (ref "CN1") (pin "49") (pinfunction "49_49") (pintype "passive+no_connect"))
    )
    (net (code "94") (name "unconnected-(CN1-Pad50)") (class "Default")
      (node (ref "CN1") (pin "50") (pinfunction "50_50") (pintype "passive+no_connect"))
    )
    (net (code "95") (name "unconnected-(CN1-Pad51)") (class "Default")
      (node (ref "CN1") (pin "51") (pinfunction "51_51") (pintype "passive+no_connect"))
    )
    (net (code "96") (name "unconnected-(CN1-Pad52)") (class "Default")
      (node (ref "CN1") (pin "52") (pinfunction "52_52") (pintype "passive+no_connect"))
    )
    (net (code "97") (name "unconnected-(CN1-Pad53)") (class "Default")
      (node (ref "CN1") (pin "53") (pinfunction "53_53") (pintype "passive+no_connect"))
    )
    (net (code "98") (name "unconnected-(CN1-Pad56)") (class "Default")
      (node (ref "CN1") (pin "56") (pinfunction "56_56") (pintype "passive+no_connect"))
    )
    (net (code "99") (name "unconnected-(CN1-Pad58)") (class "Default")
      (node (ref "CN1") (pin "58") (pinfunction "58_58") (pintype "passive+no_connect"))
    )
    (net (code "100") (name "unconnected-(CN1-Pad60)") (class "Default")
      (node (ref "CN1") (pin "60") (pinfunction "60_60") (pintype "passive+no_connect"))
    )
    (net (code "101") (name "unconnected-(CN1-Pad62)") (class "Default")
      (node (ref "CN1") (pin "62") (pinfunction "62_62") (pintype "passive+no_connect"))
    )
    (net (code "102") (name "unconnected-(CN1-Pad64)") (class "Default")
      (node (ref "CN1") (pin "64") (pinfunction "64_64") (pintype "passive+no_connect"))
    )
    (net (code "103") (name "unconnected-(CN1-Pad66)") (class "Default")
      (node (ref "CN1") (pin "66") (pinfunction "66_66") (pintype "passive+no_connect"))
    )
    (net (code "104") (name "unconnected-(CN1-Pad67)") (class "Default")
      (node (ref "CN1") (pin "67") (pinfunction "67_67") (pintype "passive+no_connect"))
    )
    (net (code "105") (name "unconnected-(CN1-Pad68)") (class "Default")
      (node (ref "CN1") (pin "68") (pinfunction "68_68") (pintype "passive+no_connect"))
    )
    (net (code "106") (name "unconnected-(CN1-Pad69)") (class "Default")
      (node (ref "CN1") (pin "69") (pinfunction "69_69") (pintype "passive+no_connect"))
    )
    (net (code "107") (name "unconnected-(CN1-Pad70)") (class "Default")
      (node (ref "CN1") (pin "70") (pinfunction "70_70") (pintype "passive+no_connect"))
    )
    (net (code "108") (name "unconnected-(CN1-Pad71)") (class "Default")
      (node (ref "CN1") (pin "71") (pinfunction "71_71") (pintype "passive+no_connect"))
    )
    (net (code "109") (name "unconnected-(CN1-Pad74)") (class "Default")
      (node (ref "CN1") (pin "74") (pinfunction "74_74") (pintype "passive+no_connect"))
    )
    (net (code "110") (name "unconnected-(CN1-Pad76)") (class "Default")
      (node (ref "CN1") (pin "76") (pinfunction "76_76") (pintype "passive+no_connect"))
    )
    (net (code "111") (name "unconnected-(CN1-Pad78)") (class "Default")
      (node (ref "CN1") (pin "78") (pinfunction "78_78") (pintype "passive+no_connect"))
    )
    (net (code "112") (name "unconnected-(CN1-Pad80)") (class "Default")
      (node (ref "CN1") (pin "80") (pinfunction "80_80") (pintype "passive+no_connect"))
    )
    (net (code "113") (name "unconnected-(CN2-Pad2)") (class "Default")
      (node (ref "CN2") (pin "2") (pinfunction "2_2") (pintype "passive+no_connect"))
    )
    (net (code "114") (name "unconnected-(CN2-Pad4)") (class "Default")
      (node (ref "CN2") (pin "4") (pinfunction "4_4") (pintype "passive+no_connect"))
    )
    (net (code "115") (name "unconnected-(CN2-Pad6)") (class "Default")
      (node (ref "CN2") (pin "6") (pinfunction "6_6") (pintype "passive+no_connect"))
    )
    (net (code "116") (name "unconnected-(CN2-Pad7)") (class "Default")
      (node (ref "CN2") (pin "7") (pinfunction "7_7") (pintype "passive+no_connect"))
    )
    (net (code "117") (name "unconnected-(CN2-Pad8)") (class "Default")
      (node (ref "CN2") (pin "8") (pinfunction "8_8") (pintype "passive+no_connect"))
    )
    (net (code "118") (name "unconnected-(CN2-Pad9)") (class "Default")
      (node (ref "CN2") (pin "9") (pinfunction "9_9") (pintype "passive+no_connect"))
    )
    (net (code "119") (name "unconnected-(CN2-Pad10)") (class "Default")
      (node (ref "CN2") (pin "10") (pinfunction "10_10") (pintype "passive+no_connect"))
    )
    (net (code "120") (name "unconnected-(CN2-Pad11)") (class "Default")
      (node (ref "CN2") (pin "11") (pinfunction "11_11") (pintype "passive+no_connect"))
    )
    (net (code "121") (name "unconnected-(CN2-Pad12)") (class "Default")
      (node (ref "CN2") (pin "12") (pinfunction "12_12") (pintype "passive+no_connect"))
    )
    (net (code "122") (name "unconnected-(CN2-Pad13)") (class "Default")
      (node (ref "CN2") (pin "13") (pinfunction "13_13") (pintype "passive+no_connect"))
    )
    (net (code "123") (name "unconnected-(CN2-Pad14)") (class "Default")
      (node (ref "CN2") (pin "14") (pinfunction "14_14") (pintype "passive+no_connect"))
    )
    (net (code "124") (name "unconnected-(CN2-Pad15)") (class "Default")
      (node (ref "CN2") (pin "15") (pinfunction "15_15") (pintype "passive+no_connect"))
    )
    (net (code "125") (name "unconnected-(CN2-Pad16)") (class "Default")
      (node (ref "CN2") (pin "16") (pinfunction "16_16") (pintype "passive+no_connect"))
    )
    (net (code "126") (name "unconnected-(CN2-Pad17)") (class "Default")
      (node (ref "CN2") (pin "17") (pinfunction "17_17") (pintype "passive+no_connect"))
    )
    (net (code "127") (name "unconnected-(CN2-Pad18)") (class "Default")
      (node (ref "CN2") (pin "18") (pinfunction "18_18") (pintype "passive+no_connect"))
    )
    (net (code "128") (name "unconnected-(CN2-Pad19)") (class "Default")
      (node (ref "CN2") (pin "19") (pinfunction "19_19") (pintype "passive+no_connect"))
    )
    (net (code "129") (name "unconnected-(CN2-Pad20)") (class "Default")
      (node (ref "CN2") (pin "20") (pinfunction "20_20") (pintype "passive+no_connect"))
    )
    (net (code "130") (name "unconnected-(CN2-Pad21)") (class "Default")
      (node (ref "CN2") (pin "21") (pinfunction "21_21") (pintype "passive+no_connect"))
    )
    (net (code "131") (name "unconnected-(CN2-Pad22)") (class "Default")
      (node (ref "CN2") (pin "22") (pinfunction "22_22") (pintype "passive+no_connect"))
    )
    (net (code "132") (name "unconnected-(CN2-Pad25)") (class "Default")
      (node (ref "CN2") (pin "25") (pinfunction "25_25") (pintype "passive+no_connect"))
    )
    (net (code "133") (name "unconnected-(CN2-Pad26)") (class "Default")
      (node (ref "CN2") (pin "26") (pinfunction "26_26") (pintype "passive+no_connect"))
    )
    (net (code "134") (name "unconnected-(CN2-Pad27)") (class "Default")
      (node (ref "CN2") (pin "27") (pinfunction "27_27") (pintype "passive+no_connect"))
    )
    (net (code "135") (name "unconnected-(CN2-Pad28)") (class "Default")
      (node (ref "CN2") (pin "28") (pinfunction "28_28") (pintype "passive+no_connect"))
    )
    (net (code "136") (name "unconnected-(CN2-Pad29)") (class "Default")
      (node (ref "CN2") (pin "29") (pinfunction "29_29") (pintype "passive+no_connect"))
    )
    (net (code "137") (name "unconnected-(CN2-Pad30)") (class "Default")
      (node (ref "CN2") (pin "30") (pinfunction "30_30") (pintype "passive+no_connect"))
    )
    (net (code "138") (name "unconnected-(CN2-Pad31)") (class "Default")
      (node (ref "CN2") (pin "31") (pinfunction "31_31") (pintype "passive+no_connect"))
    )
    (net (code "139") (name "unconnected-(CN2-Pad32)") (class "Default")
      (node (ref "CN2") (pin "32") (pinfunction "32_32") (pintype "passive+no_connect"))
    )
    (net (code "140") (name "unconnected-(CN2-Pad35)") (class "Default")
      (node (ref "CN2") (pin "35") (pinfunction "35_35") (pintype "passive+no_connect"))
    )
    (net (code "141") (name "unconnected-(CN2-Pad37)") (class "Default")
      (node (ref "CN2") (pin "37") (pinfunction "37_37") (pintype "passive+no_connect"))
    )
    (net (code "142") (name "unconnected-(CN2-Pad39)") (class "Default")
      (node (ref "CN2") (pin "39") (pinfunction "39_39") (pintype "passive+no_connect"))
    )
    (net (code "143") (name "unconnected-(CN2-Pad41)") (class "Default")
      (node (ref "CN2") (pin "41") (pinfunction "41_41") (pintype "passive+no_connect"))
    )
    (net (code "144") (name "unconnected-(CN2-Pad45)") (class "Default")
      (node (ref "CN2") (pin "45") (pinfunction "45_45") (pintype "passive+no_connect"))
    )
    (net (code "145") (name "unconnected-(CN2-Pad47)") (class "Default")
      (node (ref "CN2") (pin "47") (pinfunction "47_47") (pintype "passive+no_connect"))
    )
    (net (code "146") (name "unconnected-(CN2-Pad49)") (class "Default")
      (node (ref "CN2") (pin "49") (pinfunction "49_49") (pintype "passive+no_connect"))
    )
    (net (code "147") (name "unconnected-(CN2-Pad51)") (class "Default")
      (node (ref "CN2") (pin "51") (pinfunction "51_51") (pintype "passive+no_connect"))
    )
    (net (code "148") (name "unconnected-(CN2-Pad53)") (class "Default")
      (node (ref "CN2") (pin "53") (pinfunction "53_53") (pintype "passive+no_connect"))
    )
    (net (code "149") (name "unconnected-(CN2-Pad55)") (class "Default")
      (node (ref "CN2") (pin "55") (pinfunction "55_55") (pintype "passive+no_connect"))
    )
    (net (code "150") (name "unconnected-(CN2-Pad59)") (class "Default")
      (node (ref "CN2") (pin "59") (pinfunction "59_59") (pintype "passive+no_connect"))
    )
    (net (code "151") (name "unconnected-(CN2-Pad61)") (class "Default")
      (node (ref "CN2") (pin "61") (pinfunction "61_61") (pintype "passive+no_connect"))
    )
    (net (code "152") (name "unconnected-(CN2-Pad62)") (class "Default")
      (node (ref "CN2") (pin "62") (pinfunction "62_62") (pintype "passive+no_connect"))
    )
    (net (code "153") (name "unconnected-(CN2-Pad63)") (class "Default")
      (node (ref "CN2") (pin "63") (pinfunction "63_63") (pintype "passive+no_connect"))
    )
    (net (code "154") (name "unconnected-(CN2-Pad64)") (class "Default")
      (node (ref "CN2") (pin "64") (pinfunction "64_64") (pintype "passive+no_connect"))
    )
    (net (code "155") (name "unconnected-(CN2-Pad65)") (class "Default")
      (node (ref "CN2") (pin "65") (pinfunction "65_65") (pintype "passive+no_connect"))
    )
    (net (code "156") (name "unconnected-(CN2-Pad66)") (class "Default")
      (node (ref "CN2") (pin "66") (pinfunction "66_66") (pintype "passive+no_connect"))
    )
    (net (code "157") (name "unconnected-(CN2-Pad67)") (class "Default")
      (node (ref "CN2") (pin "67") (pinfunction "67_67") (pintype "passive+no_connect"))
    )
    (net (code "158") (name "unconnected-(CN2-Pad68)") (class "Default")
      (node (ref "CN2") (pin "68") (pinfunction "68_68") (pintype "passive+no_connect"))
    )
    (net (code "159") (name "unconnected-(CN2-Pad71)") (class "Default")
      (node (ref "CN2") (pin "71") (pinfunction "71_71") (pintype "passive+no_connect"))
    )
    (net (code "160") (name "unconnected-(CN2-Pad72)") (class "Default")
      (node (ref "CN2") (pin "72") (pinfunction "72_72") (pintype "passive+no_connect"))
    )
    (net (code "161") (name "unconnected-(J2-Pad8)") (class "Default")
      (node (ref "J2") (pin "8") (pinfunction "8_8") (pintype "passive+no_connect"))
    )
    (net (code "162") (name "unconnected-(J2-Pad9)") (class "Default")
      (node (ref "J2") (pin "9") (pinfunction "9_9") (pintype "passive+no_connect"))
    )
    (net (code "163") (name "unconnected-(J2-Pad11)") (class "Default")
      (node (ref "J2") (pin "11") (pinfunction "11_11") (pintype "passive+no_connect"))
    )
    (net (code "164") (name "unconnected-(J2-Pad12)") (class "Default")
      (node (ref "J2") (pin "12") (pinfunction "12_12") (pintype "passive+no_connect"))
    )
    (net (code "165") (name "unconnected-(J2-Pad13)") (class "Default")
      (node (ref "J2") (pin "13") (pinfunction "13_13") (pintype "passive+no_connect"))
    )
    (net (code "166") (name "unconnected-(J2-Pad14)") (class "Default")
      (node (ref "J2") (pin "14") (pinfunction "14_14") (pintype "passive+no_connect"))
    )
    (net (code "167") (name "unconnected-(J2-Pad16)") (class "Default")
      (node (ref "J2") (pin "16") (pinfunction "16_16") (pintype "passive+no_connect"))
    )
    (net (code "168") (name "unconnected-(J2-Pad18)") (class "Default")
      (node (ref "J2") (pin "18") (pinfunction "18_18") (pintype "passive+no_connect"))
    )
    (net (code "169") (name "unconnected-(J2-Pad20)") (class "Default")
      (node (ref "J2") (pin "20") (pinfunction "20_20") (pintype "passive+no_connect"))
    )
    (net (code "170") (name "unconnected-(S1-Pad3)") (class "Default")
      (node (ref "S1") (pin "3") (pinfunction "3_3") (pintype "passive+no_connect"))
    )
    (net (code "171") (name "unconnected-(U4-NC-Pad1)") (class "Default")
      (node (ref "U4") (pin "1") (pinfunction "NC_1") (pintype "passive+no_connect"))
    )
    (net (code "172") (name "unconnected-(U4-NC-Pad2)") (class "Default")
      (node (ref "U4") (pin "2") (pinfunction "NC_2") (pintype "passive+no_connect"))
    )
    (net (code "173") (name "unconnected-(U4-NC-Pad3)") (class "Default")
      (node (ref "U4") (pin "3") (pinfunction "NC_3") (pintype "passive+no_connect"))
    )
    (net (code "174") (name "unconnected-(U4-NC-Pad4)") (class "Default")
      (node (ref "U4") (pin "4") (pinfunction "NC_4") (pintype "passive+no_connect"))
    )
    (net (code "175") (name "unconnected-(U4-NC-Pad5)") (class "Default")
      (node (ref "U4") (pin "5") (pinfunction "NC_5") (pintype "passive+no_connect"))
    )
    (net (code "176") (name "unconnected-(U4-NC-Pad6)") (class "Default")
      (node (ref "U4") (pin "6") (pinfunction "NC_6") (pintype "passive+no_connect"))
    )
    (net (code "177") (name "unconnected-(U4-NC-Pad7)") (class "Default")
      (node (ref "U4") (pin "7") (pinfunction "NC_7") (pintype "passive+no_connect"))
    )
    (net (code "178") (name "unconnected-(U4-NC-Pad14)") (class "Default")
      (node (ref "U4") (pin "14") (pinfunction "NC_14") (pintype "passive+no_connect"))
    )
    (net (code "179") (name "unconnected-(U4-NC-Pad15)") (class "Default")
      (node (ref "U4") (pin "15") (pinfunction "NC_15") (pintype "passive+no_connect"))
    )
    (net (code "180") (name "unconnected-(U4-NC-Pad16)") (class "Default")
      (node (ref "U4") (pin "16") (pinfunction "NC_16") (pintype "passive+no_connect"))
    )
    (net (code "181") (name "unconnected-(U4-NC-Pad17)") (class "Default")
      (node (ref "U4") (pin "17") (pinfunction "NC_17") (pintype "passive+no_connect"))
    )
    (net (code "182") (name "unconnected-(U4-NC-Pad19)") (class "Default")
      (node (ref "U4") (pin "19") (pinfunction "NC_19") (pintype "passive+no_connect"))
    )
    (net (code "183") (name "unconnected-(U4-NC-Pad20)") (class "Default")
      (node (ref "U4") (pin "20") (pinfunction "NC_20") (pintype "passive+no_connect"))
    )
    (net (code "184") (name "unconnected-(U4-NC-Pad21)") (class "Default")
      (node (ref "U4") (pin "21") (pinfunction "NC_21") (pintype "passive+no_connect"))
    )
  )
)
